# Dimmer_Board_Rev_0_1.net
KiCad netlist of a schematic drawn in EAGLE
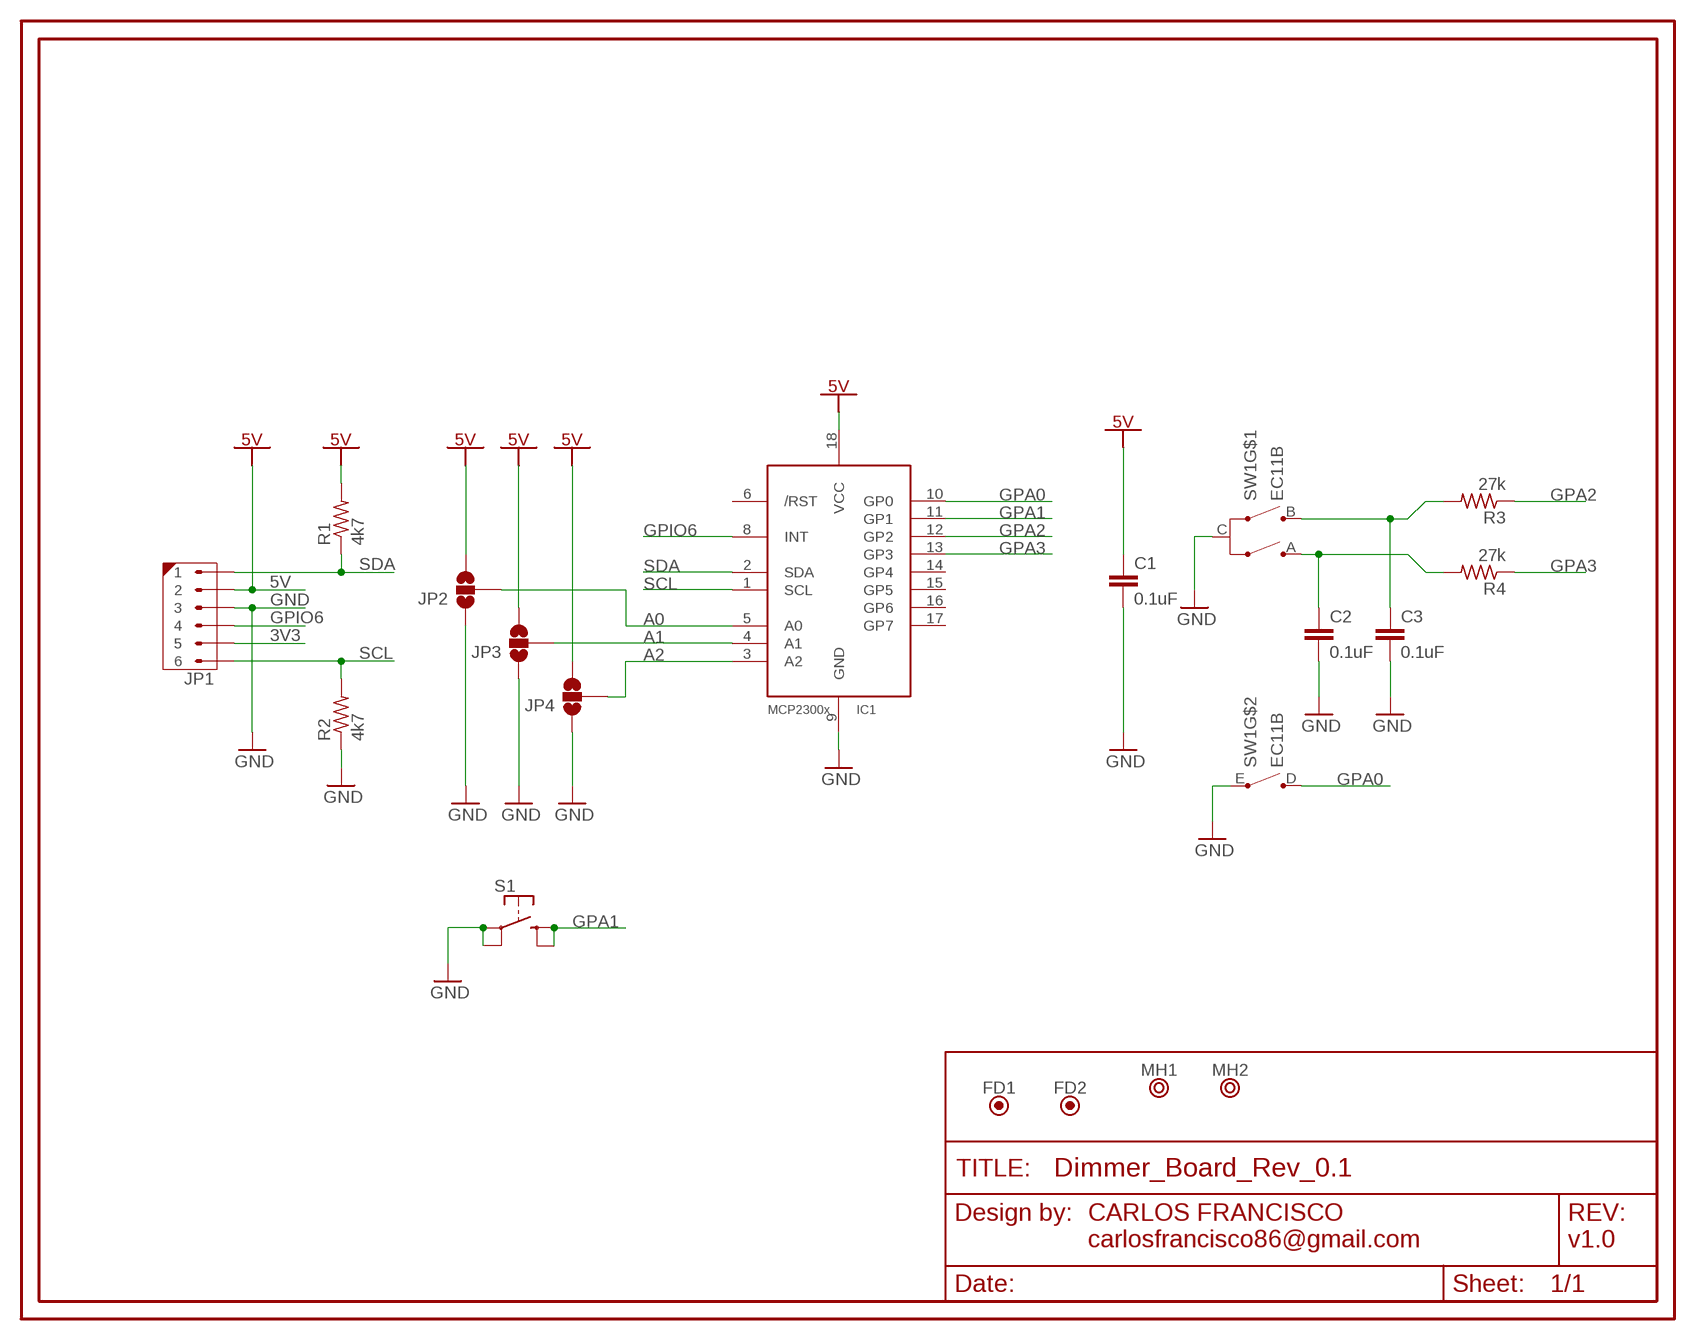
[diagram p0: schematic, sheet 1]

(export (version "E")
  (design (tool "Eeschema 10.0.6"))
  (components
    (comp (ref "C1")
      (value "0.1uF")
      (footprint "eagle-import:C0805")
      (libsource (lib "eagle-import") (part "C-EUC0805"))
    )
    (comp (ref "C2")
      (value "0.1uF")
      (footprint "eagle-import:C0805")
      (libsource (lib "eagle-import") (part "C-EUC0805"))
    )
    (comp (ref "C3")
      (value "0.1uF")
      (footprint "eagle-import:C0805")
      (libsource (lib "eagle-import") (part "C-EUC0805"))
    )
    (comp (ref "FD1")
      (value "FIDUCIALBFID")
      (footprint "eagle-import:BOARD_FIDUCIAL")
      (libsource (lib "eagle-import") (part "FIDUCIALBFID"))
    )
    (comp (ref "FD2")
      (value "FIDUCIALBFID")
      (footprint "eagle-import:BOARD_FIDUCIAL")
      (libsource (lib "eagle-import") (part "FIDUCIALBFID"))
    )
    (comp (ref "IC1")
      (value "MCP23008/SO")
      (footprint "eagle-import:SO18W")
      (libsource (lib "eagle-import") (part "MCP23008/SO"))
    )
    (comp (ref "JP1")
      (value "6X1THT_254MM")
      (footprint "eagle-import:HDRV6W63P254_6X1_1520X280H680")
      (libsource (lib "eagle-import") (part "6X1THT_254MM"))
    )
    (comp (ref "JP2")
      (value "JUMPER-SMT_3_NO_SILK")
      (footprint "eagle-import:SMT-JUMPER_3_NO_SILK")
      (libsource (lib "eagle-import") (part "JUMPER-SMT_3_NO_SILK"))
    )
    (comp (ref "JP3")
      (value "JUMPER-SMT_3_NO_SILK")
      (footprint "eagle-import:SMT-JUMPER_3_NO_SILK")
      (libsource (lib "eagle-import") (part "JUMPER-SMT_3_NO_SILK"))
    )
    (comp (ref "JP4")
      (value "JUMPER-SMT_3_NO_SILK")
      (footprint "eagle-import:SMT-JUMPER_3_NO_SILK")
      (libsource (lib "eagle-import") (part "JUMPER-SMT_3_NO_SILK"))
    )
    (comp (ref "MH1")
      (value "MOUNTING_HOLE3.5MM")
      (footprint "eagle-import:MTGP500H350")
      (libsource (lib "eagle-import") (part "MOUNTING_HOLE3.5MM"))
    )
    (comp (ref "MH2")
      (value "MOUNTING_HOLE3.5MM")
      (footprint "eagle-import:MTGP500H350")
      (libsource (lib "eagle-import") (part "MOUNTING_HOLE3.5MM"))
    )
    (comp (ref "R1")
      (value "4k7")
      (footprint "eagle-import:R0805")
      (libsource (lib "eagle-import") (part "R-US_R0805"))
    )
    (comp (ref "R2")
      (value "4k7")
      (footprint "eagle-import:R0805")
      (libsource (lib "eagle-import") (part "R-US_R0805"))
    )
    (comp (ref "R3")
      (value "27k")
      (footprint "eagle-import:R0805")
      (libsource (lib "eagle-import") (part "R-US_R0805"))
    )
    (comp (ref "R4")
      (value "27k")
      (footprint "eagle-import:R0805")
      (libsource (lib "eagle-import") (part "R-US_R0805"))
    )
    (comp (ref "S1")
      (value "BUTTON-4KSC")
      (footprint "eagle-import:KSC_X")
      (libsource (lib "eagle-import") (part "BUTTON-4KSC"))
    )
    (comp (ref "SW1")
      (value "EC11B")
      (footprint "eagle-import:EC11B-V")
      (libsource (lib "eagle-import") (part "EC11B-V-T"))
    )
  )
  (nets
    (net (code "1") (name "/3V3") (class "Default")
      (node (ref "JP1") (pin "5") (pinfunction "5_5") (pintype "passive"))
    )
    (net (code "2") (name "/A0") (class "Default")
      (node (ref "IC1") (pin "5") (pinfunction "A0_5") (pintype "input"))
      (node (ref "JP2") (pin "2") (pinfunction "2_2") (pintype "passive"))
    )
    (net (code "3") (name "/A1") (class "Default")
      (node (ref "IC1") (pin "4") (pinfunction "A1_4") (pintype "input"))
      (node (ref "JP3") (pin "2") (pinfunction "2_2") (pintype "passive"))
    )
    (net (code "4") (name "/A2") (class "Default")
      (node (ref "IC1") (pin "3") (pinfunction "A2_3") (pintype "input"))
      (node (ref "JP4") (pin "2") (pinfunction "2_2") (pintype "passive"))
    )
    (net (code "5") (name "/GPA0") (class "Default")
      (node (ref "IC1") (pin "10") (pinfunction "GP0_10") (pintype "bidirectional"))
      (node (ref "SW1") (pin "D") (pinfunction "D_D") (pintype "passive"))
    )
    (net (code "6") (name "/GPA1") (class "Default")
      (node (ref "IC1") (pin "11") (pinfunction "GP1_11") (pintype "bidirectional"))
      (node (ref "S1") (pin "3") (pinfunction "3_3") (pintype "passive"))
      (node (ref "S1") (pin "4") (pinfunction "4_4") (pintype "passive"))
    )
    (net (code "7") (name "/GPA2") (class "Default")
      (node (ref "IC1") (pin "12") (pinfunction "GP2_12") (pintype "bidirectional"))
      (node (ref "R3") (pin "1") (pinfunction "1_1") (pintype "passive"))
    )
    (net (code "8") (name "/GPA3") (class "Default")
      (node (ref "IC1") (pin "13") (pinfunction "GP3_13") (pintype "bidirectional"))
      (node (ref "R4") (pin "1") (pinfunction "1_1") (pintype "passive"))
    )
    (net (code "9") (name "/GPIO6") (class "Default")
      (node (ref "IC1") (pin "8") (pinfunction "INT_8") (pintype "output"))
      (node (ref "JP1") (pin "4") (pinfunction "4_4") (pintype "passive"))
    )
    (net (code "10") (name "/SCL") (class "Default")
      (node (ref "IC1") (pin "1") (pinfunction "SCL_1") (pintype "bidirectional"))
      (node (ref "JP1") (pin "6") (pinfunction "6_6") (pintype "passive"))
      (node (ref "R2") (pin "2") (pinfunction "2_2") (pintype "passive"))
    )
    (net (code "11") (name "/SDA") (class "Default")
      (node (ref "IC1") (pin "2") (pinfunction "SDA_2") (pintype "bidirectional"))
      (node (ref "JP1") (pin "1") (pinfunction "1_1") (pintype "passive"))
      (node (ref "R1") (pin "1") (pinfunction "1_1") (pintype "passive"))
    )
    (net (code "12") (name "5V") (class "Default")
      (node (ref "C1") (pin "1") (pinfunction "1_1") (pintype "passive"))
      (node (ref "IC1") (pin "18") (pinfunction "VCC_18") (pintype "power_in"))
      (node (ref "JP1") (pin "2") (pinfunction "2_2") (pintype "passive"))
      (node (ref "JP2") (pin "3") (pinfunction "3_3") (pintype "passive"))
      (node (ref "JP3") (pin "3") (pinfunction "3_3") (pintype "passive"))
      (node (ref "JP4") (pin "3") (pinfunction "3_3") (pintype "passive"))
      (node (ref "R1") (pin "2") (pinfunction "2_2") (pintype "passive"))
    )
    (net (code "13") (name "GND") (class "Default")
      (node (ref "C1") (pin "2") (pinfunction "2_2") (pintype "passive"))
      (node (ref "C2") (pin "2") (pinfunction "2_2") (pintype "passive"))
      (node (ref "C3") (pin "2") (pinfunction "2_2") (pintype "passive"))
      (node (ref "IC1") (pin "9") (pinfunction "GND_9") (pintype "power_in"))
      (node (ref "JP1") (pin "3") (pinfunction "3_3") (pintype "passive"))
      (node (ref "JP2") (pin "1") (pinfunction "1_1") (pintype "passive"))
      (node (ref "JP3") (pin "1") (pinfunction "1_1") (pintype "passive"))
      (node (ref "JP4") (pin "1") (pinfunction "1_1") (pintype "passive"))
      (node (ref "R2") (pin "1") (pinfunction "1_1") (pintype "passive"))
      (node (ref "S1") (pin "1") (pinfunction "1_1") (pintype "passive"))
      (node (ref "S1") (pin "2") (pinfunction "2_2") (pintype "passive"))
      (node (ref "SW1") (pin "C") (pinfunction "C_C") (pintype "passive"))
      (node (ref "SW1") (pin "E") (pinfunction "E_E") (pintype "passive"))
    )
    (net (code "14") (name "Net-(C2-Pad1)") (class "Default")
      (node (ref "C2") (pin "1") (pinfunction "1_1") (pintype "passive"))
      (node (ref "R4") (pin "2") (pinfunction "2_2") (pintype "passive"))
      (node (ref "SW1") (pin "A") (pinfunction "A_A") (pintype "passive"))
    )
    (net (code "15") (name "Net-(C3-Pad1)") (class "Default")
      (node (ref "C3") (pin "1") (pinfunction "1_1") (pintype "passive"))
      (node (ref "R3") (pin "2") (pinfunction "2_2") (pintype "passive"))
      (node (ref "SW1") (pin "B") (pinfunction "B_B") (pintype "passive"))
    )
    (net (code "16") (name "unconnected-(IC1-GP4-Pad14)") (class "Default")
      (node (ref "IC1") (pin "14") (pinfunction "GP4_14") (pintype "bidirectional"))
    )
    (net (code "17") (name "unconnected-(IC1-GP5-Pad15)") (class "Default")
      (node (ref "IC1") (pin "15") (pinfunction "GP5_15") (pintype "bidirectional"))
    )
    (net (code "18") (name "unconnected-(IC1-GP6-Pad16)") (class "Default")
      (node (ref "IC1") (pin "16") (pinfunction "GP6_16") (pintype "bidirectional"))
    )
    (net (code "19") (name "unconnected-(IC1-GP7-Pad17)") (class "Default")
      (node (ref "IC1") (pin "17") (pinfunction "GP7_17") (pintype "bidirectional"))
    )
    (net (code "20") (name "unconnected-(IC1-{slash}RST-Pad6)") (class "Default")
      (node (ref "IC1") (pin "6") (pinfunction "/RST_6") (pintype "input"))
    )
    (net (code "21") (name "unconnected-(MH1-Pad1)") (class "Default")
      (node (ref "MH1") (pin "1") (pinfunction "1_1") (pintype "passive"))
    )
    (net (code "22") (name "unconnected-(MH2-Pad1)") (class "Default")
      (node (ref "MH2") (pin "1") (pinfunction "1_1") (pintype "passive"))
    )
  )
)
